# EMI_TestBoard_Schematic.net
KiCad netlist of a schematic drawn in Altium Designer
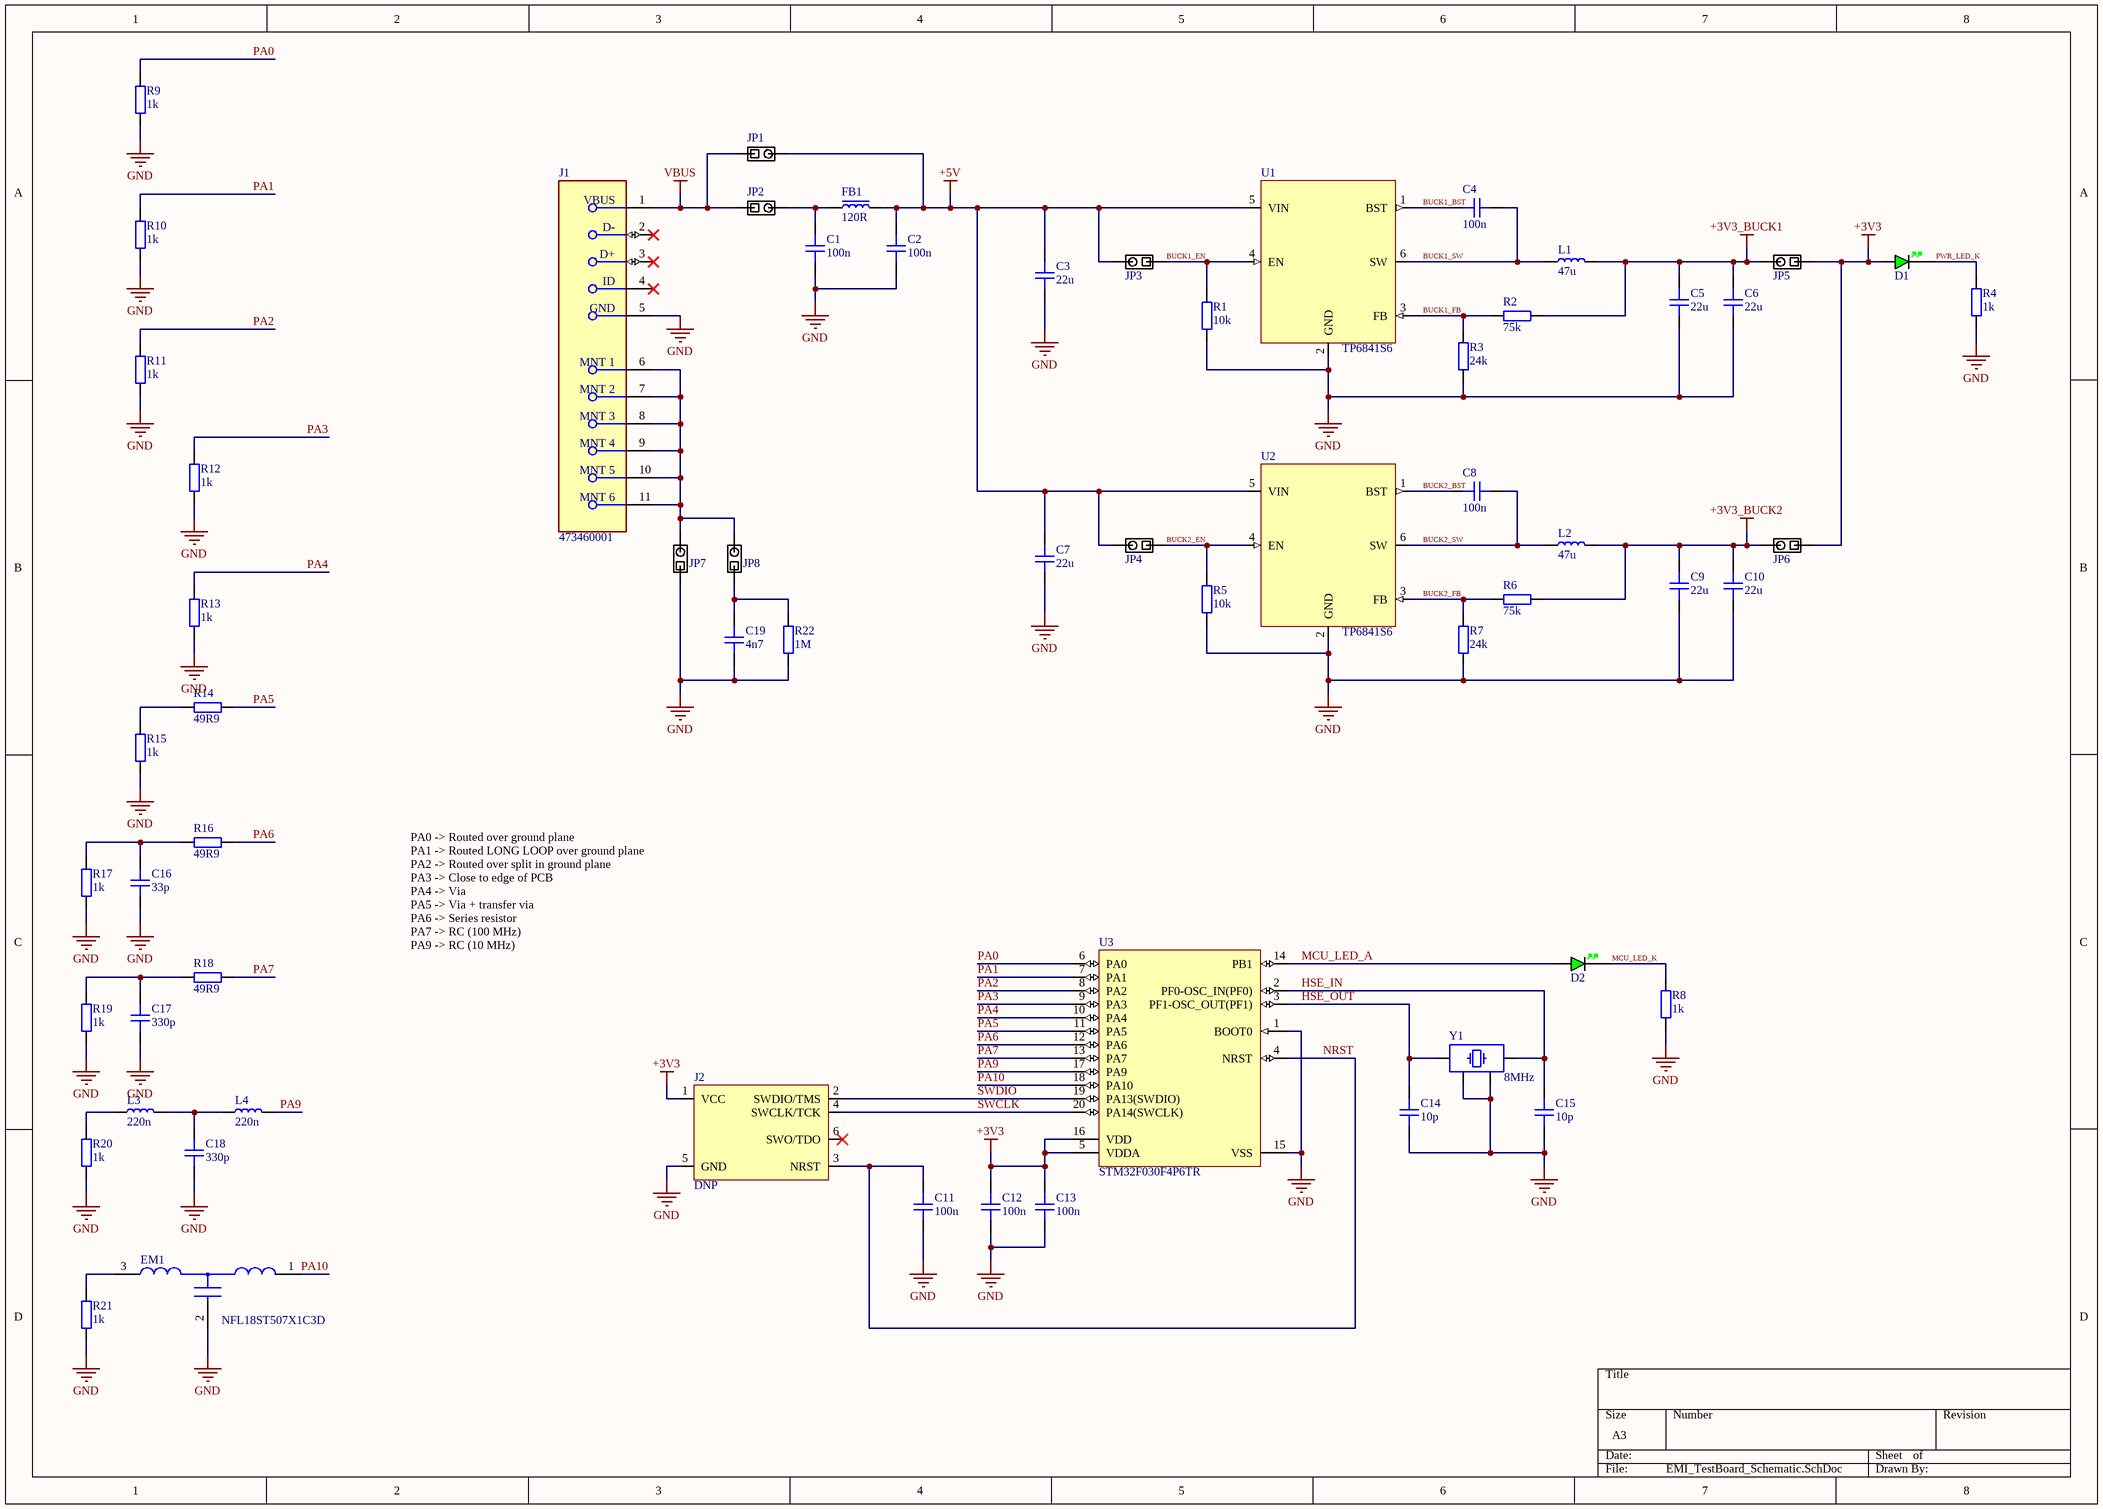
[diagram p0: EMI_TestBoard_Schematic.SchDoc]

(export (version "E")
  (design (tool "Eeschema 10.0.6"))
  (components
    (comp (ref "C1")
      (value "100n")
      (footprint "CAP_0603")
      (description "Capacitor SMD 0603 50V")
      (libsource (lib "Schematic-Lib-PhilsLab") (part "CAP_0603_50V"))
    )
    (comp (ref "C2")
      (value "100n")
      (footprint "CAP_0603")
      (description "Capacitor SMD 0603 50V")
      (libsource (lib "Schematic-Lib-PhilsLab") (part "CAP_0603_50V"))
    )
    (comp (ref "C3")
      (value "22u")
      (footprint "CAP_1210")
      (description "Capacitor SMD 1210 10V")
      (libsource (lib "Schematic-Lib-PhilsLab") (part "CAP_1210_10V"))
    )
    (comp (ref "C4")
      (value "100n")
      (footprint "CAP_0603")
      (description "Capacitor SMD 0603 50V")
      (libsource (lib "Schematic-Lib-PhilsLab") (part "CAP_0603_50V"))
    )
    (comp (ref "C5")
      (value "22u")
      (footprint "CAP_1210")
      (description "Capacitor SMD 1210 10V")
      (libsource (lib "Schematic-Lib-PhilsLab") (part "CAP_1210_10V"))
    )
    (comp (ref "C6")
      (value "22u")
      (footprint "CAP_1210")
      (description "Capacitor SMD 1210 10V")
      (libsource (lib "Schematic-Lib-PhilsLab") (part "CAP_1210_10V"))
    )
    (comp (ref "C7")
      (value "22u")
      (footprint "CAP_1210")
      (description "Capacitor SMD 1210 10V")
      (libsource (lib "Schematic-Lib-PhilsLab") (part "CAP_1210_10V"))
    )
    (comp (ref "C8")
      (value "100n")
      (footprint "CAP_0603")
      (description "Capacitor SMD 0603 50V")
      (libsource (lib "Schematic-Lib-PhilsLab") (part "CAP_0603_50V"))
    )
    (comp (ref "C9")
      (value "22u")
      (footprint "CAP_1210")
      (description "Capacitor SMD 1210 10V")
      (libsource (lib "Schematic-Lib-PhilsLab") (part "CAP_1210_10V"))
    )
    (comp (ref "C10")
      (value "22u")
      (footprint "CAP_1210")
      (description "Capacitor SMD 1210 10V")
      (libsource (lib "Schematic-Lib-PhilsLab") (part "CAP_1210_10V"))
    )
    (comp (ref "C11")
      (value "100n")
      (footprint "CAP_0603")
      (description "Capacitor SMD 0603 50V")
      (libsource (lib "Schematic-Lib-PhilsLab") (part "CAP_0603_50V"))
    )
    (comp (ref "C12")
      (value "100n")
      (footprint "CAP_0603")
      (description "Capacitor SMD 0603 50V")
      (libsource (lib "Schematic-Lib-PhilsLab") (part "CAP_0603_50V"))
    )
    (comp (ref "C13")
      (value "100n")
      (footprint "CAP_0603")
      (description "Capacitor SMD 0603 50V")
      (libsource (lib "Schematic-Lib-PhilsLab") (part "CAP_0603_50V"))
    )
    (comp (ref "C14")
      (value "10p")
      (footprint "CAP_0603")
      (description "Capacitor SMD 0603 50V")
      (libsource (lib "Schematic-Lib-PhilsLab") (part "CAP_0603_50V"))
    )
    (comp (ref "C15")
      (value "10p")
      (footprint "CAP_0603")
      (description "Capacitor SMD 0603 50V")
      (libsource (lib "Schematic-Lib-PhilsLab") (part "CAP_0603_50V"))
    )
    (comp (ref "C16")
      (value "33p")
      (footprint "CAP_0603")
      (description "Capacitor SMD 0603 50V")
      (libsource (lib "Schematic-Lib-PhilsLab") (part "CAP_0603_50V"))
    )
    (comp (ref "C17")
      (value "330p")
      (footprint "CAP_0603")
      (description "Capacitor SMD 0603 50V")
      (libsource (lib "Schematic-Lib-PhilsLab") (part "CAP_0603_50V"))
    )
    (comp (ref "C18")
      (value "330p")
      (footprint "CAP_0603")
      (description "Capacitor SMD 0603 50V")
      (libsource (lib "Schematic-Lib-PhilsLab") (part "CAP_0603_50V"))
    )
    (comp (ref "C19")
      (value "4n7")
      (footprint "CAP_0603")
      (description "Capacitor SMD 0603 50V")
      (libsource (lib "Schematic-Lib-PhilsLab") (part "CAP_0603_50V"))
    )
    (comp (ref "D1")
      (value "GREEN")
      (footprint "LED_0402_GREEN")
      (description "LED 0402 GREEN SMD")
      (libsource (lib "Schematic-Lib-PhilsLab") (part "LED_0402_GREEN"))
    )
    (comp (ref "D2")
      (value "GREEN")
      (footprint "LED_0402_GREEN")
      (description "LED 0402 GREEN SMD")
      (libsource (lib "Schematic-Lib-PhilsLab") (part "LED_0402_GREEN"))
    )
    (comp (ref "EM1")
      (value "NFL18ST507X1C3D")
      (footprint "FP-NFL18ST-MFG")
      (description "LC combined filters 25pF 110nH 200MHz 16Vdc 150mA 0603")
      (libsource (lib "Altium Content Vault") (part "0dcc21493ca9fc5ee07099c0833c53e"))
    )
    (comp (ref "FB1")
      (value "120R")
      (footprint "FB_0603")
      (description "Ferrite Bead SMD 0603")
      (libsource (lib "Schematic-Lib-PhilsLab") (part "FB_0603"))
    )
    (comp (ref "J1")
      (value "473460001")
      (footprint "FP-473460001-MFG")
      (description "USB - micro B USB 2.0 Receptacle Connector 5 Position Surface Mount, Right Angle")
      (fields (field (name "OCTOPART") "https://octopart.com/47346-0001-molex-7164928"))
      (libsource (lib "Altium Content Vault") (part "53ae1f1d9b557310b43ca686e5bb76a"))
    )
    (comp (ref "J2")
      (value "DNP")
      (footprint "TC2030-NL-FP")
      (description "Tag-Connect No-Solder SWD Debug Connector (No Legs) DO NOT PLACE")
      (fields (field (name "MANUFACTURER") "Tag-Connect"))
      (libsource (lib "Schematic-Lib-PhilsLab") (part "TC2030-NL"))
    )
    (comp (ref "JP1")
      (value "Solder Jumper")
      (footprint "SolderJumper_Single")
      (description "Solder Jumper Single 0.5mm Pitch")
      (libsource (lib "Schematic-Lib-PhilsLab") (part "SolderJumper_Single"))
    )
    (comp (ref "JP2")
      (value "Solder Jumper")
      (footprint "SolderJumper_Single")
      (description "Solder Jumper Single 0.5mm Pitch")
      (libsource (lib "Schematic-Lib-PhilsLab") (part "SolderJumper_Single"))
    )
    (comp (ref "JP3")
      (value "Solder Jumper")
      (footprint "SolderJumper_Single")
      (description "Solder Jumper Single 0.5mm Pitch")
      (libsource (lib "Schematic-Lib-PhilsLab") (part "SolderJumper_Single"))
    )
    (comp (ref "JP4")
      (value "Solder Jumper")
      (footprint "SolderJumper_Single")
      (description "Solder Jumper Single 0.5mm Pitch")
      (libsource (lib "Schematic-Lib-PhilsLab") (part "SolderJumper_Single"))
    )
    (comp (ref "JP5")
      (value "Solder Jumper")
      (footprint "SolderJumper_Single")
      (description "Solder Jumper Single 0.5mm Pitch")
      (libsource (lib "Schematic-Lib-PhilsLab") (part "SolderJumper_Single"))
    )
    (comp (ref "JP6")
      (value "Solder Jumper")
      (footprint "SolderJumper_Single")
      (description "Solder Jumper Single 0.5mm Pitch")
      (libsource (lib "Schematic-Lib-PhilsLab") (part "SolderJumper_Single"))
    )
    (comp (ref "JP7")
      (value "Solder Jumper")
      (footprint "SolderJumper_Single")
      (description "Solder Jumper Single 0.5mm Pitch")
      (libsource (lib "Schematic-Lib-PhilsLab") (part "SolderJumper_Single"))
    )
    (comp (ref "JP8")
      (value "Solder Jumper")
      (footprint "SolderJumper_Single")
      (description "Solder Jumper Single 0.5mm Pitch")
      (libsource (lib "Schematic-Lib-PhilsLab") (part "SolderJumper_Single"))
    )
    (comp (ref "L1")
      (value "47u")
      (footprint "MWSA0603S")
      (description "Power Inductor SMD Sunlord MWSA0603S")
      (fields (field (name "MANUFACTURER") "Sunlord") (field (name "MANUFACTURER PART NUMBER") "MWSA0603S-"))
      (libsource (lib "Schematic-Lib-PhilsLab") (part "MWSA0603S"))
    )
    (comp (ref "L2")
      (value "47u")
      (footprint "MWSA0603S")
      (description "Power Inductor SMD Sunlord MWSA0603S")
      (fields (field (name "MANUFACTURER") "Sunlord") (field (name "MANUFACTURER PART NUMBER") "MWSA0603S-"))
      (libsource (lib "Schematic-Lib-PhilsLab") (part "MWSA0603S"))
    )
    (comp (ref "L3")
      (value "220n")
      (footprint "IND_0603")
      (description "Inductor SMD 0603")
      (libsource (lib "Schematic-Lib-PhilsLab") (part "IND_0603"))
    )
    (comp (ref "L4")
      (value "220n")
      (footprint "IND_0603")
      (description "Inductor SMD 0603")
      (libsource (lib "Schematic-Lib-PhilsLab") (part "IND_0603"))
    )
    (comp (ref "R1")
      (value "10k")
      (footprint "RES_0603")
      (description "Resistor SMD 0603")
      (libsource (lib "Schematic-Lib-PhilsLab") (part "RES_0603"))
    )
    (comp (ref "R2")
      (value "75k")
      (footprint "RES_0603")
      (description "Resistor SMD 0603")
      (libsource (lib "Schematic-Lib-PhilsLab") (part "RES_0603"))
    )
    (comp (ref "R3")
      (value "24k")
      (footprint "RES_0603")
      (description "Resistor SMD 0603")
      (libsource (lib "Schematic-Lib-PhilsLab") (part "RES_0603"))
    )
    (comp (ref "R4")
      (value "1k")
      (footprint "RES_0603")
      (description "Resistor SMD 0603")
      (libsource (lib "Schematic-Lib-PhilsLab") (part "RES_0603"))
    )
    (comp (ref "R5")
      (value "10k")
      (footprint "RES_0603")
      (description "Resistor SMD 0603")
      (libsource (lib "Schematic-Lib-PhilsLab") (part "RES_0603"))
    )
    (comp (ref "R6")
      (value "75k")
      (footprint "RES_0603")
      (description "Resistor SMD 0603")
      (libsource (lib "Schematic-Lib-PhilsLab") (part "RES_0603"))
    )
    (comp (ref "R7")
      (value "24k")
      (footprint "RES_0603")
      (description "Resistor SMD 0603")
      (libsource (lib "Schematic-Lib-PhilsLab") (part "RES_0603"))
    )
    (comp (ref "R8")
      (value "1k")
      (footprint "RES_0603")
      (description "Resistor SMD 0603")
      (libsource (lib "Schematic-Lib-PhilsLab") (part "RES_0603"))
    )
    (comp (ref "R9")
      (value "1k")
      (footprint "RES_0603")
      (description "Resistor SMD 0603")
      (libsource (lib "Schematic-Lib-PhilsLab") (part "RES_0603"))
    )
    (comp (ref "R10")
      (value "1k")
      (footprint "RES_0603")
      (description "Resistor SMD 0603")
      (libsource (lib "Schematic-Lib-PhilsLab") (part "RES_0603"))
    )
    (comp (ref "R11")
      (value "1k")
      (footprint "RES_0603")
      (description "Resistor SMD 0603")
      (libsource (lib "Schematic-Lib-PhilsLab") (part "RES_0603"))
    )
    (comp (ref "R12")
      (value "1k")
      (footprint "RES_0603")
      (description "Resistor SMD 0603")
      (libsource (lib "Schematic-Lib-PhilsLab") (part "RES_0603"))
    )
    (comp (ref "R13")
      (value "1k")
      (footprint "RES_0603")
      (description "Resistor SMD 0603")
      (libsource (lib "Schematic-Lib-PhilsLab") (part "RES_0603"))
    )
    (comp (ref "R14")
      (value "49R9")
      (footprint "RES_0603")
      (description "Resistor SMD 0603")
      (libsource (lib "Schematic-Lib-PhilsLab") (part "RES_0603"))
    )
    (comp (ref "R15")
      (value "1k")
      (footprint "RES_0603")
      (description "Resistor SMD 0603")
      (libsource (lib "Schematic-Lib-PhilsLab") (part "RES_0603"))
    )
    (comp (ref "R16")
      (value "49R9")
      (footprint "RES_0603")
      (description "Resistor SMD 0603")
      (libsource (lib "Schematic-Lib-PhilsLab") (part "RES_0603"))
    )
    (comp (ref "R17")
      (value "1k")
      (footprint "RES_0603")
      (description "Resistor SMD 0603")
      (libsource (lib "Schematic-Lib-PhilsLab") (part "RES_0603"))
    )
    (comp (ref "R18")
      (value "49R9")
      (footprint "RES_0603")
      (description "Resistor SMD 0603")
      (libsource (lib "Schematic-Lib-PhilsLab") (part "RES_0603"))
    )
    (comp (ref "R19")
      (value "1k")
      (footprint "RES_0603")
      (description "Resistor SMD 0603")
      (libsource (lib "Schematic-Lib-PhilsLab") (part "RES_0603"))
    )
    (comp (ref "R20")
      (value "1k")
      (footprint "RES_0603")
      (description "Resistor SMD 0603")
      (libsource (lib "Schematic-Lib-PhilsLab") (part "RES_0603"))
    )
    (comp (ref "R21")
      (value "1k")
      (footprint "RES_0603")
      (description "Resistor SMD 0603")
      (libsource (lib "Schematic-Lib-PhilsLab") (part "RES_0603"))
    )
    (comp (ref "R22")
      (value "1M")
      (footprint "RES_0603")
      (description "Resistor SMD 0603")
      (libsource (lib "Schematic-Lib-PhilsLab") (part "RES_0603"))
    )
    (comp (ref "U1")
      (value "TP6841S6")
      (footprint "SOT-23-6")
      (description "40V 0.8A 800kHz Synchronous Step-Down Converter")
      (fields (field (name "MANUFACTURER") "TECH PUBLIC"))
      (libsource (lib "Schematic-Lib-PhilsLab") (part "TP6841S6"))
    )
    (comp (ref "U2")
      (value "TP6841S6")
      (footprint "SOT-23-6")
      (description "40V 0.8A 800kHz Synchronous Step-Down Converter")
      (fields (field (name "MANUFACTURER") "TECH PUBLIC"))
      (libsource (lib "Schematic-Lib-PhilsLab") (part "TP6841S6"))
    )
    (comp (ref "U3")
      (value "STM32F030F4P6TR")
      (footprint "STM-TSSOP20_M")
      (fields (field (name "MANUFACTURER") "STMicroelectronics"))
      (libsource (lib "Altium Content Vault") (part "MC-ARM-STM32F030-TSSOP20"))
    )
    (comp (ref "Y1")
      (value "8MHz")
      (footprint "XTAL_3225")
      (description "Crystal SMD 24MHz 10PPM 7pF 3225")
      (fields (field (name "MANUFACTURER") "Epson"))
      (libsource (lib "Schematic-Lib-PhilsLab") (part "TSX-3225_24.0000MF15X-AC"))
    )
  )
  (nets
    (net (code "1") (name "+3V3") (class "Default")
      (node (ref "C12") (pin "2") (pinfunction "2_2") (pintype "passive"))
      (node (ref "C13") (pin "2") (pinfunction "2_2") (pintype "passive"))
      (node (ref "D1") (pin "A") (pinfunction "A_A") (pintype "passive"))
      (node (ref "J2") (pin "1") (pinfunction "VCC_1") (pintype "passive"))
      (node (ref "JP5") (pin "1") (pinfunction "1_1") (pintype "passive"))
      (node (ref "JP6") (pin "1") (pinfunction "1_1") (pintype "passive"))
      (node (ref "U3") (pin "16") (pinfunction "VDD_16") (pintype "power_in"))
      (node (ref "U3") (pin "5") (pinfunction "VDDA_5") (pintype "power_in"))
    )
    (net (code "2") (name "+3V3_BUCK1") (class "Default")
      (node (ref "C5") (pin "2") (pinfunction "2_2") (pintype "passive"))
      (node (ref "C6") (pin "2") (pinfunction "2_2") (pintype "passive"))
      (node (ref "JP5") (pin "2") (pinfunction "2_2") (pintype "passive"))
      (node (ref "L1") (pin "2") (pinfunction "2_2") (pintype "passive"))
      (node (ref "R2") (pin "1") (pinfunction "1_1") (pintype "passive"))
    )
    (net (code "3") (name "+3V3_BUCK2") (class "Default")
      (node (ref "C10") (pin "2") (pinfunction "2_2") (pintype "passive"))
      (node (ref "C9") (pin "2") (pinfunction "2_2") (pintype "passive"))
      (node (ref "JP6") (pin "2") (pinfunction "2_2") (pintype "passive"))
      (node (ref "L2") (pin "2") (pinfunction "2_2") (pintype "passive"))
      (node (ref "R6") (pin "1") (pinfunction "1_1") (pintype "passive"))
    )
    (net (code "4") (name "+5V") (class "Default")
      (node (ref "C2") (pin "2") (pinfunction "2_2") (pintype "passive"))
      (node (ref "C3") (pin "2") (pinfunction "2_2") (pintype "passive"))
      (node (ref "C7") (pin "2") (pinfunction "2_2") (pintype "passive"))
      (node (ref "FB1") (pin "2") (pinfunction "2_2") (pintype "passive"))
      (node (ref "JP1") (pin "2") (pinfunction "2_2") (pintype "passive"))
      (node (ref "JP3") (pin "2") (pinfunction "2_2") (pintype "passive"))
      (node (ref "JP4") (pin "2") (pinfunction "2_2") (pintype "passive"))
      (node (ref "U1") (pin "5") (pinfunction "VIN_5") (pintype "power_in"))
      (node (ref "U2") (pin "5") (pinfunction "VIN_5") (pintype "power_in"))
    )
    (net (code "5") (name "/BUCK1_BST") (class "Default")
      (node (ref "C4") (pin "2") (pinfunction "2_2") (pintype "passive"))
      (node (ref "U1") (pin "1") (pinfunction "BST_1") (pintype "output"))
    )
    (net (code "6") (name "/BUCK1_EN") (class "Default")
      (node (ref "JP3") (pin "1") (pinfunction "1_1") (pintype "passive"))
      (node (ref "R1") (pin "2") (pinfunction "2_2") (pintype "passive"))
      (node (ref "U1") (pin "4") (pinfunction "EN_4") (pintype "input"))
    )
    (net (code "7") (name "/BUCK1_FB") (class "Default")
      (node (ref "R2") (pin "2") (pinfunction "2_2") (pintype "passive"))
      (node (ref "R3") (pin "2") (pinfunction "2_2") (pintype "passive"))
      (node (ref "U1") (pin "3") (pinfunction "FB_3") (pintype "input"))
    )
    (net (code "8") (name "/BUCK1_SW") (class "Default")
      (node (ref "C4") (pin "1") (pinfunction "1_1") (pintype "passive"))
      (node (ref "L1") (pin "1") (pinfunction "1_1") (pintype "passive"))
      (node (ref "U1") (pin "6") (pinfunction "SW_6") (pintype "power_in"))
    )
    (net (code "9") (name "/BUCK2_BST") (class "Default")
      (node (ref "C8") (pin "2") (pinfunction "2_2") (pintype "passive"))
      (node (ref "U2") (pin "1") (pinfunction "BST_1") (pintype "output"))
    )
    (net (code "10") (name "/BUCK2_EN") (class "Default")
      (node (ref "JP4") (pin "1") (pinfunction "1_1") (pintype "passive"))
      (node (ref "R5") (pin "2") (pinfunction "2_2") (pintype "passive"))
      (node (ref "U2") (pin "4") (pinfunction "EN_4") (pintype "input"))
    )
    (net (code "11") (name "/BUCK2_FB") (class "Default")
      (node (ref "R6") (pin "2") (pinfunction "2_2") (pintype "passive"))
      (node (ref "R7") (pin "2") (pinfunction "2_2") (pintype "passive"))
      (node (ref "U2") (pin "3") (pinfunction "FB_3") (pintype "input"))
    )
    (net (code "12") (name "/BUCK2_SW") (class "Default")
      (node (ref "C8") (pin "1") (pinfunction "1_1") (pintype "passive"))
      (node (ref "L2") (pin "1") (pinfunction "1_1") (pintype "passive"))
      (node (ref "U2") (pin "6") (pinfunction "SW_6") (pintype "power_in"))
    )
    (net (code "13") (name "/HSE_IN") (class "Default")
      (node (ref "C15") (pin "2") (pinfunction "2_2") (pintype "passive"))
      (node (ref "U3") (pin "2") (pinfunction "PF0-OSC_IN(PF0)_2") (pintype "bidirectional"))
      (node (ref "Y1") (pin "3") (pinfunction "3_3") (pintype "passive"))
    )
    (net (code "14") (name "/HSE_OUT") (class "Default")
      (node (ref "C14") (pin "2") (pinfunction "2_2") (pintype "passive"))
      (node (ref "U3") (pin "3") (pinfunction "PF1-OSC_OUT(PF1)_3") (pintype "bidirectional"))
      (node (ref "Y1") (pin "1") (pinfunction "1_1") (pintype "passive"))
    )
    (net (code "15") (name "/MCU_LED_A") (class "Default")
      (node (ref "D2") (pin "A") (pinfunction "A_A") (pintype "passive"))
      (node (ref "U3") (pin "14") (pinfunction "PB1_14") (pintype "bidirectional"))
    )
    (net (code "16") (name "/MCU_LED_K") (class "Default")
      (node (ref "D2") (pin "K") (pinfunction "K_K") (pintype "passive"))
      (node (ref "R8") (pin "2") (pinfunction "2_2") (pintype "passive"))
    )
    (net (code "17") (name "/NRST") (class "Default")
      (node (ref "C11") (pin "2") (pinfunction "2_2") (pintype "passive"))
      (node (ref "J2") (pin "3") (pinfunction "NRST_3") (pintype "passive"))
      (node (ref "U3") (pin "4") (pinfunction "NRST_4") (pintype "bidirectional"))
    )
    (net (code "18") (name "/PA0") (class "Default")
      (node (ref "R9") (pin "2") (pinfunction "2_2") (pintype "passive"))
      (node (ref "U3") (pin "6") (pinfunction "PA0_6") (pintype "bidirectional"))
    )
    (net (code "19") (name "/PA1") (class "Default")
      (node (ref "R10") (pin "2") (pinfunction "2_2") (pintype "passive"))
      (node (ref "U3") (pin "7") (pinfunction "PA1_7") (pintype "bidirectional"))
    )
    (net (code "20") (name "/PA2") (class "Default")
      (node (ref "R11") (pin "2") (pinfunction "2_2") (pintype "passive"))
      (node (ref "U3") (pin "8") (pinfunction "PA2_8") (pintype "bidirectional"))
    )
    (net (code "21") (name "/PA3") (class "Default")
      (node (ref "R12") (pin "2") (pinfunction "2_2") (pintype "passive"))
      (node (ref "U3") (pin "9") (pinfunction "PA3_9") (pintype "bidirectional"))
    )
    (net (code "22") (name "/PA4") (class "Default")
      (node (ref "R13") (pin "2") (pinfunction "2_2") (pintype "passive"))
      (node (ref "U3") (pin "10") (pinfunction "PA4_10") (pintype "bidirectional"))
    )
    (net (code "23") (name "/PA5") (class "Default")
      (node (ref "R14") (pin "1") (pinfunction "1_1") (pintype "passive"))
      (node (ref "U3") (pin "11") (pinfunction "PA5_11") (pintype "bidirectional"))
    )
    (net (code "24") (name "/PA6") (class "Default")
      (node (ref "R16") (pin "1") (pinfunction "1_1") (pintype "passive"))
      (node (ref "U3") (pin "12") (pinfunction "PA6_12") (pintype "bidirectional"))
    )
    (net (code "25") (name "/PA7") (class "Default")
      (node (ref "R18") (pin "1") (pinfunction "1_1") (pintype "passive"))
      (node (ref "U3") (pin "13") (pinfunction "PA7_13") (pintype "bidirectional"))
    )
    (net (code "26") (name "/PA9") (class "Default")
      (node (ref "L4") (pin "2") (pinfunction "2_2") (pintype "passive"))
      (node (ref "U3") (pin "17") (pinfunction "PA9_17") (pintype "bidirectional"))
    )
    (net (code "27") (name "/PA10") (class "Default")
      (node (ref "EM1") (pin "1") (pinfunction "Input_1") (pintype "passive"))
      (node (ref "U3") (pin "18") (pinfunction "PA10_18") (pintype "bidirectional"))
    )
    (net (code "28") (name "/PWR_LED_K") (class "Default")
      (node (ref "D1") (pin "K") (pinfunction "K_K") (pintype "passive"))
      (node (ref "R4") (pin "2") (pinfunction "2_2") (pintype "passive"))
    )
    (net (code "29") (name "/SWCLK") (class "Default")
      (node (ref "J2") (pin "4") (pinfunction "SWCLK/TCK_4") (pintype "passive"))
      (node (ref "U3") (pin "20") (pinfunction "PA14(SWCLK)_20") (pintype "bidirectional"))
    )
    (net (code "30") (name "/SWDIO") (class "Default")
      (node (ref "J2") (pin "2") (pinfunction "SWDIO/TMS_2") (pintype "passive"))
      (node (ref "U3") (pin "19") (pinfunction "PA13(SWDIO)_19") (pintype "bidirectional"))
    )
    (net (code "31") (name "GND") (class "Default")
      (node (ref "C1") (pin "1") (pinfunction "1_1") (pintype "passive"))
      (node (ref "C10") (pin "1") (pinfunction "1_1") (pintype "passive"))
      (node (ref "C11") (pin "1") (pinfunction "1_1") (pintype "passive"))
      (node (ref "C12") (pin "1") (pinfunction "1_1") (pintype "passive"))
      (node (ref "C13") (pin "1") (pinfunction "1_1") (pintype "passive"))
      (node (ref "C14") (pin "1") (pinfunction "1_1") (pintype "passive"))
      (node (ref "C15") (pin "1") (pinfunction "1_1") (pintype "passive"))
      (node (ref "C16") (pin "1") (pinfunction "1_1") (pintype "passive"))
      (node (ref "C17") (pin "1") (pinfunction "1_1") (pintype "passive"))
      (node (ref "C18") (pin "1") (pinfunction "1_1") (pintype "passive"))
      (node (ref "C19") (pin "1") (pinfunction "1_1") (pintype "passive"))
      (node (ref "C2") (pin "1") (pinfunction "1_1") (pintype "passive"))
      (node (ref "C3") (pin "1") (pinfunction "1_1") (pintype "passive"))
      (node (ref "C5") (pin "1") (pinfunction "1_1") (pintype "passive"))
      (node (ref "C6") (pin "1") (pinfunction "1_1") (pintype "passive"))
      (node (ref "C7") (pin "1") (pinfunction "1_1") (pintype "passive"))
      (node (ref "C9") (pin "1") (pinfunction "1_1") (pintype "passive"))
      (node (ref "EM1") (pin "2") (pinfunction "GND_2") (pintype "power_in"))
      (node (ref "J1") (pin "5") (pinfunction "GND_5") (pintype "power_in"))
      (node (ref "J2") (pin "5") (pinfunction "GND_5") (pintype "passive"))
      (node (ref "JP7") (pin "1") (pinfunction "1_1") (pintype "passive"))
      (node (ref "R1") (pin "1") (pinfunction "1_1") (pintype "passive"))
      (node (ref "R10") (pin "1") (pinfunction "1_1") (pintype "passive"))
      (node (ref "R11") (pin "1") (pinfunction "1_1") (pintype "passive"))
      (node (ref "R12") (pin "1") (pinfunction "1_1") (pintype "passive"))
      (node (ref "R13") (pin "1") (pinfunction "1_1") (pintype "passive"))
      (node (ref "R15") (pin "1") (pinfunction "1_1") (pintype "passive"))
      (node (ref "R17") (pin "1") (pinfunction "1_1") (pintype "passive"))
      (node (ref "R19") (pin "1") (pinfunction "1_1") (pintype "passive"))
      (node (ref "R20") (pin "1") (pinfunction "1_1") (pintype "passive"))
      (node (ref "R21") (pin "1") (pinfunction "1_1") (pintype "passive"))
      (node (ref "R22") (pin "1") (pinfunction "1_1") (pintype "passive"))
      (node (ref "R3") (pin "1") (pinfunction "1_1") (pintype "passive"))
      (node (ref "R4") (pin "1") (pinfunction "1_1") (pintype "passive"))
      (node (ref "R5") (pin "1") (pinfunction "1_1") (pintype "passive"))
      (node (ref "R7") (pin "1") (pinfunction "1_1") (pintype "passive"))
      (node (ref "R8") (pin "1") (pinfunction "1_1") (pintype "passive"))
      (node (ref "R9") (pin "1") (pinfunction "1_1") (pintype "passive"))
      (node (ref "U1") (pin "2") (pinfunction "GND_2") (pintype "power_in"))
      (node (ref "U2") (pin "2") (pinfunction "GND_2") (pintype "power_in"))
      (node (ref "U3") (pin "1") (pinfunction "BOOT0_1") (pintype "input"))
      (node (ref "U3") (pin "15") (pinfunction "VSS_15") (pintype "power_in"))
      (node (ref "Y1") (pin "2") (pinfunction "2_2") (pintype "passive"))
      (node (ref "Y1") (pin "4") (pinfunction "4_4") (pintype "passive"))
    )
    (net (code "32") (name "Net-(C1-Pad2)") (class "Default")
      (node (ref "C1") (pin "2") (pinfunction "2_2") (pintype "passive"))
      (node (ref "FB1") (pin "1") (pinfunction "1_1") (pintype "passive"))
      (node (ref "JP2") (pin "2") (pinfunction "2_2") (pintype "passive"))
    )
    (net (code "33") (name "Net-(C16-Pad2)") (class "Default")
      (node (ref "C16") (pin "2") (pinfunction "2_2") (pintype "passive"))
      (node (ref "R16") (pin "2") (pinfunction "2_2") (pintype "passive"))
      (node (ref "R17") (pin "2") (pinfunction "2_2") (pintype "passive"))
    )
    (net (code "34") (name "Net-(C17-Pad2)") (class "Default")
      (node (ref "C17") (pin "2") (pinfunction "2_2") (pintype "passive"))
      (node (ref "R18") (pin "2") (pinfunction "2_2") (pintype "passive"))
      (node (ref "R19") (pin "2") (pinfunction "2_2") (pintype "passive"))
    )
    (net (code "35") (name "Net-(C18-Pad2)") (class "Default")
      (node (ref "C18") (pin "2") (pinfunction "2_2") (pintype "passive"))
      (node (ref "L3") (pin "2") (pinfunction "2_2") (pintype "passive"))
      (node (ref "L4") (pin "1") (pinfunction "1_1") (pintype "passive"))
    )
    (net (code "36") (name "Net-(C19-Pad2)") (class "Default")
      (node (ref "C19") (pin "2") (pinfunction "2_2") (pintype "passive"))
      (node (ref "JP8") (pin "1") (pinfunction "1_1") (pintype "passive"))
      (node (ref "R22") (pin "2") (pinfunction "2_2") (pintype "passive"))
    )
    (net (code "37") (name "Net-(EM1-Output)") (class "Default")
      (node (ref "EM1") (pin "3") (pinfunction "Output_3") (pintype "passive"))
      (node (ref "R21") (pin "2") (pinfunction "2_2") (pintype "passive"))
    )
    (net (code "38") (name "Net-(J1-MNT_1)") (class "Default")
      (node (ref "J1") (pin "10") (pinfunction "MNT_5_10") (pintype "passive"))
      (node (ref "J1") (pin "11") (pinfunction "MNT_6_11") (pintype "passive"))
      (node (ref "J1") (pin "6") (pinfunction "MNT_1_6") (pintype "passive"))
      (node (ref "J1") (pin "7") (pinfunction "MNT_2_7") (pintype "passive"))
      (node (ref "J1") (pin "8") (pinfunction "MNT_3_8") (pintype "passive"))
      (node (ref "J1") (pin "9") (pinfunction "MNT_4_9") (pintype "passive"))
      (node (ref "JP7") (pin "2") (pinfunction "2_2") (pintype "passive"))
      (node (ref "JP8") (pin "2") (pinfunction "2_2") (pintype "passive"))
    )
    (net (code "39") (name "Net-(L3-Pad1)") (class "Default")
      (node (ref "L3") (pin "1") (pinfunction "1_1") (pintype "passive"))
      (node (ref "R20") (pin "2") (pinfunction "2_2") (pintype "passive"))
    )
    (net (code "40") (name "Net-(R14-Pad2)") (class "Default")
      (node (ref "R14") (pin "2") (pinfunction "2_2") (pintype "passive"))
      (node (ref "R15") (pin "2") (pinfunction "2_2") (pintype "passive"))
    )
    (net (code "41") (name "VBUS") (class "Default")
      (node (ref "J1") (pin "1") (pinfunction "VBUS_1") (pintype "power_in"))
      (node (ref "JP1") (pin "1") (pinfunction "1_1") (pintype "passive"))
      (node (ref "JP2") (pin "1") (pinfunction "1_1") (pintype "passive"))
    )
    (net (code "42") (name "unconnected-(J1-D+-Pad3)") (class "Default")
      (node (ref "J1") (pin "3") (pinfunction "D+_3") (pintype "bidirectional+no_connect"))
    )
    (net (code "43") (name "unconnected-(J1-D--Pad2)") (class "Default")
      (node (ref "J1") (pin "2") (pinfunction "D-_2") (pintype "bidirectional+no_connect"))
    )
    (net (code "44") (name "unconnected-(J1-ID-Pad4)") (class "Default")
      (node (ref "J1") (pin "4") (pinfunction "ID_4") (pintype "passive+no_connect"))
    )
    (net (code "45") (name "unconnected-(J2-SWO{slash}TDO-Pad6)") (class "Default")
      (node (ref "J2") (pin "6") (pinfunction "SWO/TDO_6") (pintype "passive+no_connect"))
    )
  )
)
